# pthbadge_batt_non_sao_CCC_Version.net
KiCad netlist of a schematic drawn in EAGLE
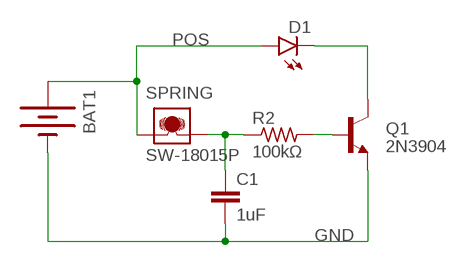
[diagram p0: schematic, sheet 1]

(export (version "E")
  (design (tool "Eeschema 10.0.6"))
  (components
    (comp (ref "BAT1")
      (value "BATTERY20PTH")
      (footprint "eagle-import:BATTCOM_20MM_PTH")
      (libsource (lib "eagle-import") (part "BATTERY20PTH"))
    )
    (comp (ref "C1")
      (value "1uF")
      (footprint "eagle-import:CAP-PTH-SMALL")
      (libsource (lib "eagle-import") (part "CAPPTH"))
    )
    (comp (ref "D1")
      (value "LED5MM")
      (footprint "eagle-import:LED5MM")
      (libsource (lib "eagle-import") (part "LED5MM"))
    )
    (comp (ref "Q1")
      (value "2N3904")
      (footprint "eagle-import:TO-92-AMMO")
      (libsource (lib "eagle-import") (part "TRANSISTOR_NPNTO-92-AMMO"))
    )
    (comp (ref "R2")
      (value "100kΩ")
      (footprint "eagle-import:0207_10")
      (libsource (lib "eagle-import") (part "R-US_0207/10"))
    )
    (comp (ref "SPRING")
      (value "SW-18015P")
      (footprint "eagle-import:SW-18015P")
      (fields (field (name "MF") "FARNELL") (field (name "MPN") "CM4400-1."))
      (libsource (lib "eagle-import") (part "SW-18015P"))
    )
  )
  (nets
    (net (code "1") (name "/GND") (class "Default")
      (node (ref "BAT1") (pin "2") (pinfunction "-_2") (pintype "power_in"))
      (node (ref "C1") (pin "2") (pinfunction "2_2") (pintype "passive"))
      (node (ref "Q1") (pin "1") (pinfunction "E_1") (pintype "passive"))
    )
    (net (code "2") (name "/POS") (class "Default")
      (node (ref "BAT1") (pin "1") (pinfunction "+_1") (pintype "power_in"))
      (node (ref "D1") (pin "A") (pinfunction "A_A") (pintype "passive"))
      (node (ref "SPRING") (pin "1") (pinfunction "1_1") (pintype "passive"))
    )
    (net (code "3") (name "Net-(C1-Pad1)") (class "Default")
      (node (ref "C1") (pin "1") (pinfunction "1_1") (pintype "passive"))
      (node (ref "R2") (pin "1") (pinfunction "1_1") (pintype "passive"))
      (node (ref "SPRING") (pin "2") (pinfunction "2_2") (pintype "passive"))
    )
    (net (code "4") (name "Net-(D1-C)") (class "Default")
      (node (ref "D1") (pin "K") (pinfunction "C_K") (pintype "passive"))
      (node (ref "Q1") (pin "3") (pinfunction "C_3") (pintype "passive"))
    )
    (net (code "5") (name "Net-(Q1-B)") (class "Default")
      (node (ref "Q1") (pin "2") (pinfunction "B_2") (pintype "passive"))
      (node (ref "R2") (pin "2") (pinfunction "2_2") (pintype "passive"))
    )
  )
)
